# comm.net
KiCad netlist of a schematic drawn in Altium Designer
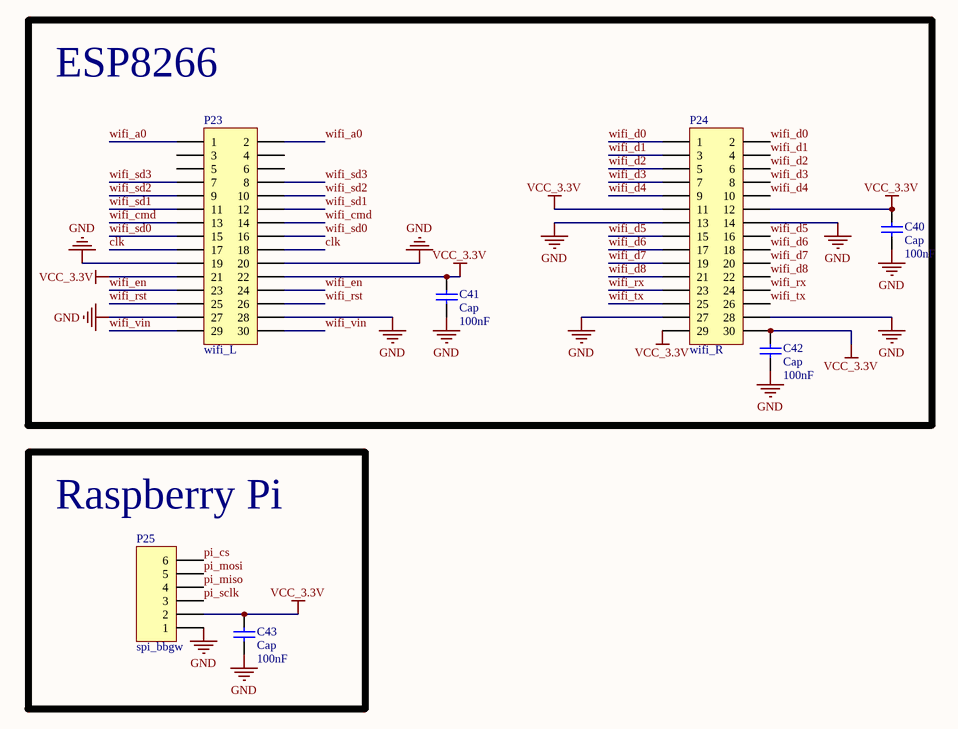
[diagram p0: comm.SchDoc]

(export (version "E")
  (design (tool "Eeschema 10.0.6"))
  (components
    (comp (ref "C40")
      (value "Cap")
      (footprint "RAD-0.1")
      (description "Capacitor")
      (fields (field (name "ALTIUM_VALUE") "100nF") (field (name "PUBLISHER") "Altium Limited"))
      (libsource (lib "Miscellaneous Devices") (part "Cap"))
    )
    (comp (ref "C41")
      (value "Cap")
      (footprint "RAD-0.1")
      (description "Capacitor")
      (fields (field (name "ALTIUM_VALUE") "100nF") (field (name "PUBLISHER") "Altium Limited"))
      (libsource (lib "Miscellaneous Devices") (part "Cap"))
    )
    (comp (ref "C42")
      (value "Cap")
      (footprint "RAD-0.1")
      (description "Capacitor")
      (fields (field (name "ALTIUM_VALUE") "100nF") (field (name "PUBLISHER") "Altium Limited"))
      (libsource (lib "Miscellaneous Devices") (part "Cap"))
    )
    (comp (ref "C43")
      (value "Cap")
      (footprint "RAD-0.1")
      (description "Capacitor")
      (fields (field (name "ALTIUM_VALUE") "100nF") (field (name "PUBLISHER") "Altium Limited"))
      (libsource (lib "Miscellaneous Devices") (part "Cap"))
    )
    (comp (ref "P23")
      (value "wifi_L")
      (footprint "HDR2X15")
      (description "Header, 15-Pin, Dual row")
      (fields (field (name "PUBLISHER") "Altium Limited"))
      (libsource (lib "Miscellaneous Connectors") (part "Header 15X2"))
    )
    (comp (ref "P24")
      (value "wifi_R")
      (footprint "HDR2X15")
      (description "Header, 15-Pin, Dual row")
      (fields (field (name "PUBLISHER") "Altium Limited"))
      (libsource (lib "Miscellaneous Connectors") (part "Header 15X2"))
    )
    (comp (ref "P25")
      (value "spi_bbgw")
      (footprint "HDR1X6")
      (description "Header, 6-Pin")
      (fields (field (name "PUBLISHER") "Altium Limited"))
      (libsource (lib "Miscellaneous Connectors") (part "Header 6"))
    )
  )
  (nets
    (net (code "1") (name "/clk") (class "Default")
      (node (ref "P23") (pin "17") (pinfunction "17_17") (pintype "passive"))
      (node (ref "P23") (pin "18") (pinfunction "18_18") (pintype "passive"))
    )
    (net (code "2") (name "/pi_cs") (class "Default")
      (node (ref "P25") (pin "6") (pinfunction "6_6") (pintype "passive"))
    )
    (net (code "3") (name "/pi_miso") (class "Default")
      (node (ref "P25") (pin "4") (pinfunction "4_4") (pintype "passive"))
    )
    (net (code "4") (name "/pi_mosi") (class "Default")
      (node (ref "P25") (pin "5") (pinfunction "5_5") (pintype "passive"))
    )
    (net (code "5") (name "/pi_sclk") (class "Default")
      (node (ref "P25") (pin "3") (pinfunction "3_3") (pintype "passive"))
    )
    (net (code "6") (name "/wifi_a0") (class "Default")
      (node (ref "P23") (pin "1") (pinfunction "1_1") (pintype "passive"))
      (node (ref "P23") (pin "2") (pinfunction "2_2") (pintype "passive"))
    )
    (net (code "7") (name "/wifi_cmd") (class "Default")
      (node (ref "P23") (pin "13") (pinfunction "13_13") (pintype "passive"))
      (node (ref "P23") (pin "14") (pinfunction "14_14") (pintype "passive"))
    )
    (net (code "8") (name "/wifi_d0") (class "Default")
      (node (ref "P24") (pin "1") (pinfunction "1_1") (pintype "passive"))
      (node (ref "P24") (pin "2") (pinfunction "2_2") (pintype "passive"))
    )
    (net (code "9") (name "/wifi_d1") (class "Default")
      (node (ref "P24") (pin "3") (pinfunction "3_3") (pintype "passive"))
      (node (ref "P24") (pin "4") (pinfunction "4_4") (pintype "passive"))
    )
    (net (code "10") (name "/wifi_d2") (class "Default")
      (node (ref "P24") (pin "5") (pinfunction "5_5") (pintype "passive"))
      (node (ref "P24") (pin "6") (pinfunction "6_6") (pintype "passive"))
    )
    (net (code "11") (name "/wifi_d3") (class "Default")
      (node (ref "P24") (pin "7") (pinfunction "7_7") (pintype "passive"))
      (node (ref "P24") (pin "8") (pinfunction "8_8") (pintype "passive"))
    )
    (net (code "12") (name "/wifi_d4") (class "Default")
      (node (ref "P24") (pin "10") (pinfunction "10_10") (pintype "passive"))
      (node (ref "P24") (pin "9") (pinfunction "9_9") (pintype "passive"))
    )
    (net (code "13") (name "/wifi_d5") (class "Default")
      (node (ref "P24") (pin "15") (pinfunction "15_15") (pintype "passive"))
      (node (ref "P24") (pin "16") (pinfunction "16_16") (pintype "passive"))
    )
    (net (code "14") (name "/wifi_d6") (class "Default")
      (node (ref "P24") (pin "17") (pinfunction "17_17") (pintype "passive"))
      (node (ref "P24") (pin "18") (pinfunction "18_18") (pintype "passive"))
    )
    (net (code "15") (name "/wifi_d7") (class "Default")
      (node (ref "P24") (pin "19") (pinfunction "19_19") (pintype "passive"))
      (node (ref "P24") (pin "20") (pinfunction "20_20") (pintype "passive"))
    )
    (net (code "16") (name "/wifi_d8") (class "Default")
      (node (ref "P24") (pin "21") (pinfunction "21_21") (pintype "passive"))
      (node (ref "P24") (pin "22") (pinfunction "22_22") (pintype "passive"))
    )
    (net (code "17") (name "/wifi_en") (class "Default")
      (node (ref "P23") (pin "23") (pinfunction "23_23") (pintype "passive"))
      (node (ref "P23") (pin "24") (pinfunction "24_24") (pintype "passive"))
    )
    (net (code "18") (name "/wifi_rst") (class "Default")
      (node (ref "P23") (pin "25") (pinfunction "25_25") (pintype "passive"))
      (node (ref "P23") (pin "26") (pinfunction "26_26") (pintype "passive"))
    )
    (net (code "19") (name "/wifi_rx") (class "Default")
      (node (ref "P24") (pin "23") (pinfunction "23_23") (pintype "passive"))
      (node (ref "P24") (pin "24") (pinfunction "24_24") (pintype "passive"))
    )
    (net (code "20") (name "/wifi_sd0") (class "Default")
      (node (ref "P23") (pin "15") (pinfunction "15_15") (pintype "passive"))
      (node (ref "P23") (pin "16") (pinfunction "16_16") (pintype "passive"))
    )
    (net (code "21") (name "/wifi_sd1") (class "Default")
      (node (ref "P23") (pin "11") (pinfunction "11_11") (pintype "passive"))
      (node (ref "P23") (pin "12") (pinfunction "12_12") (pintype "passive"))
    )
    (net (code "22") (name "/wifi_sd2") (class "Default")
      (node (ref "P23") (pin "10") (pinfunction "10_10") (pintype "passive"))
      (node (ref "P23") (pin "9") (pinfunction "9_9") (pintype "passive"))
    )
    (net (code "23") (name "/wifi_sd3") (class "Default")
      (node (ref "P23") (pin "7") (pinfunction "7_7") (pintype "passive"))
      (node (ref "P23") (pin "8") (pinfunction "8_8") (pintype "passive"))
    )
    (net (code "24") (name "/wifi_tx") (class "Default")
      (node (ref "P24") (pin "25") (pinfunction "25_25") (pintype "passive"))
      (node (ref "P24") (pin "26") (pinfunction "26_26") (pintype "passive"))
    )
    (net (code "25") (name "/wifi_vin") (class "Default")
      (node (ref "P23") (pin "29") (pinfunction "29_29") (pintype "passive"))
      (node (ref "P23") (pin "30") (pinfunction "30_30") (pintype "passive"))
    )
    (net (code "26") (name "GND") (class "Default")
      (node (ref "C40") (pin "1") (pinfunction "1_1") (pintype "passive"))
      (node (ref "C41") (pin "1") (pinfunction "1_1") (pintype "passive"))
      (node (ref "C42") (pin "1") (pinfunction "1_1") (pintype "passive"))
      (node (ref "C43") (pin "1") (pinfunction "1_1") (pintype "passive"))
      (node (ref "P23") (pin "19") (pinfunction "19_19") (pintype "passive"))
      (node (ref "P23") (pin "20") (pinfunction "20_20") (pintype "passive"))
      (node (ref "P23") (pin "27") (pinfunction "27_27") (pintype "passive"))
      (node (ref "P23") (pin "28") (pinfunction "28_28") (pintype "passive"))
      (node (ref "P24") (pin "13") (pinfunction "13_13") (pintype "passive"))
      (node (ref "P24") (pin "14") (pinfunction "14_14") (pintype "passive"))
      (node (ref "P24") (pin "27") (pinfunction "27_27") (pintype "passive"))
      (node (ref "P24") (pin "28") (pinfunction "28_28") (pintype "passive"))
      (node (ref "P25") (pin "1") (pinfunction "1_1") (pintype "passive"))
    )
    (net (code "27") (name "VCC_3.3V") (class "Default")
      (node (ref "C40") (pin "2") (pinfunction "2_2") (pintype "passive"))
      (node (ref "C41") (pin "2") (pinfunction "2_2") (pintype "passive"))
      (node (ref "C42") (pin "2") (pinfunction "2_2") (pintype "passive"))
      (node (ref "C43") (pin "2") (pinfunction "2_2") (pintype "passive"))
      (node (ref "P23") (pin "21") (pinfunction "21_21") (pintype "passive"))
      (node (ref "P23") (pin "22") (pinfunction "22_22") (pintype "passive"))
      (node (ref "P24") (pin "11") (pinfunction "11_11") (pintype "passive"))
      (node (ref "P24") (pin "12") (pinfunction "12_12") (pintype "passive"))
      (node (ref "P24") (pin "29") (pinfunction "29_29") (pintype "passive"))
      (node (ref "P24") (pin "30") (pinfunction "30_30") (pintype "passive"))
      (node (ref "P25") (pin "2") (pinfunction "2_2") (pintype "passive"))
    )
    (net (code "28") (name "unconnected-(P23-Pad3)") (class "Default")
      (node (ref "P23") (pin "3") (pinfunction "3_3") (pintype "passive"))
    )
    (net (code "29") (name "unconnected-(P23-Pad4)") (class "Default")
      (node (ref "P23") (pin "4") (pinfunction "4_4") (pintype "passive"))
    )
    (net (code "30") (name "unconnected-(P23-Pad5)") (class "Default")
      (node (ref "P23") (pin "5") (pinfunction "5_5") (pintype "passive"))
    )
    (net (code "31") (name "unconnected-(P23-Pad6)") (class "Default")
      (node (ref "P23") (pin "6") (pinfunction "6_6") (pintype "passive"))
    )
  )
)
